# mcu_board_b.net
KiCad netlist of a schematic drawn in EAGLE
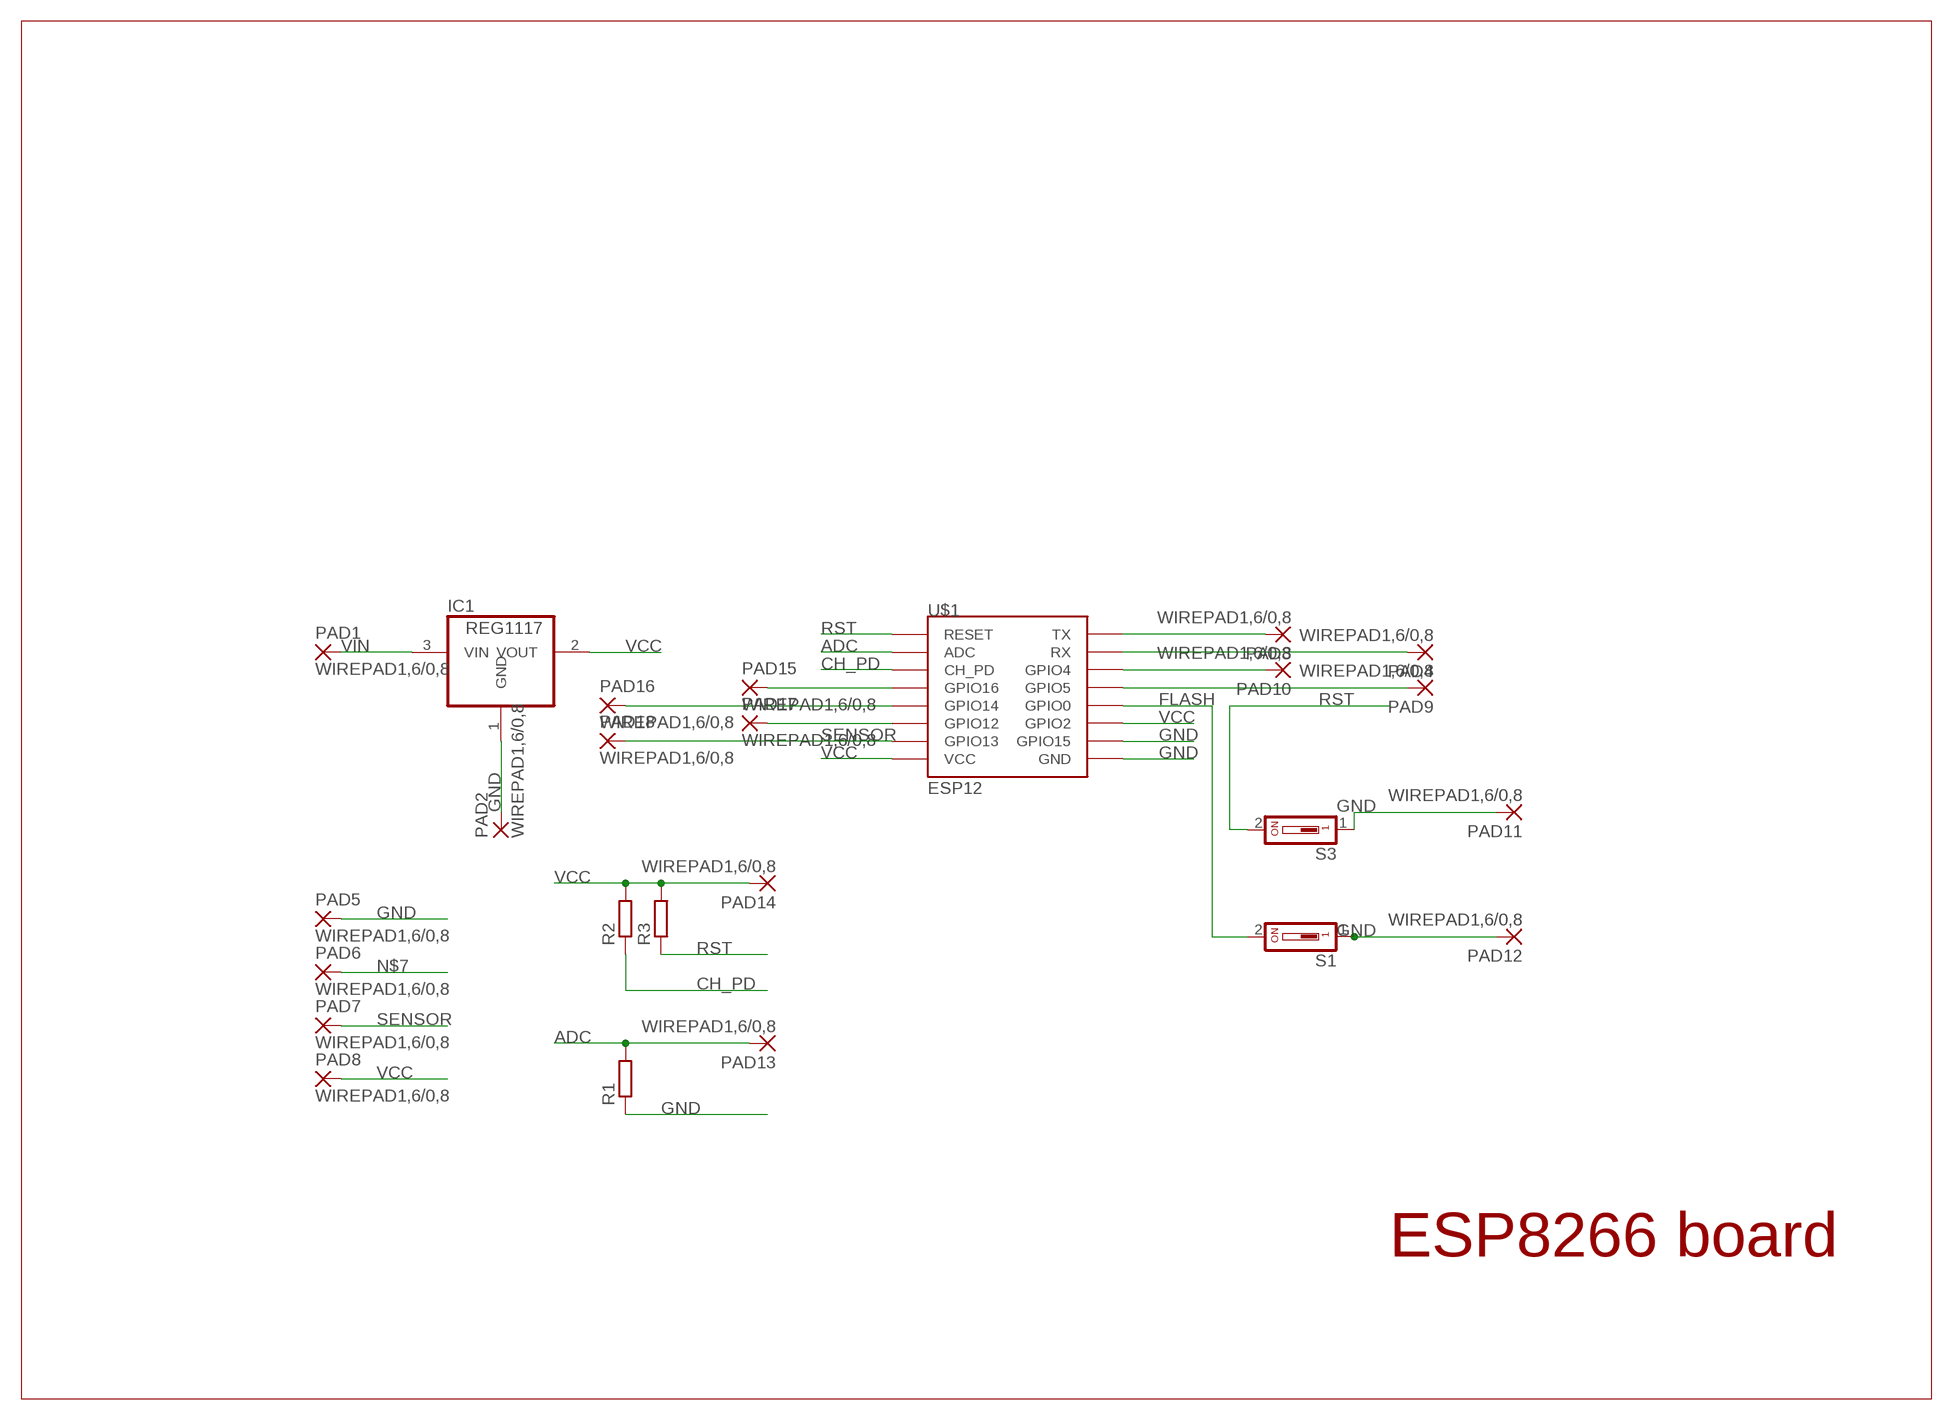
[diagram p0: schematic, sheet 1]

(export (version "E")
  (design (tool "Eeschema 10.0.6"))
  (components
    (comp (ref "IC1")
      (value "REG1117")
      (footprint "eagle-import:SOT223")
      (libsource (lib "eagle-import") (part "REG1117"))
    )
    (comp (ref "PAD1")
      (value "WIREPAD1,6/0,8")
      (footprint "eagle-import:1,6_0,8")
      (libsource (lib "eagle-import") (part "WIREPAD1,6/0,8"))
    )
    (comp (ref "PAD2")
      (value "WIREPAD1,6/0,8")
      (footprint "eagle-import:1,6_0,8")
      (libsource (lib "eagle-import") (part "WIREPAD1,6/0,8"))
    )
    (comp (ref "PAD3")
      (value "WIREPAD1,6/0,8")
      (footprint "eagle-import:1,6_0,8")
      (libsource (lib "eagle-import") (part "WIREPAD1,6/0,8"))
    )
    (comp (ref "PAD4")
      (value "WIREPAD1,6/0,8")
      (footprint "eagle-import:1,6_0,8")
      (libsource (lib "eagle-import") (part "WIREPAD1,6/0,8"))
    )
    (comp (ref "PAD5")
      (value "WIREPAD1,6/0,8")
      (footprint "eagle-import:1,6_0,8")
      (libsource (lib "eagle-import") (part "WIREPAD1,6/0,8"))
    )
    (comp (ref "PAD6")
      (value "WIREPAD1,6/0,8")
      (footprint "eagle-import:1,6_0,8")
      (libsource (lib "eagle-import") (part "WIREPAD1,6/0,8"))
    )
    (comp (ref "PAD7")
      (value "WIREPAD1,6/0,8")
      (footprint "eagle-import:1,6_0,8")
      (libsource (lib "eagle-import") (part "WIREPAD1,6/0,8"))
    )
    (comp (ref "PAD8")
      (value "WIREPAD1,6/0,8")
      (footprint "eagle-import:1,6_0,8")
      (libsource (lib "eagle-import") (part "WIREPAD1,6/0,8"))
    )
    (comp (ref "PAD9")
      (value "WIREPAD1,6/0,8")
      (footprint "eagle-import:1,6_0,8")
      (libsource (lib "eagle-import") (part "WIREPAD1,6/0,8"))
    )
    (comp (ref "PAD10")
      (value "WIREPAD1,6/0,8")
      (footprint "eagle-import:1,6_0,8")
      (libsource (lib "eagle-import") (part "WIREPAD1,6/0,8"))
    )
    (comp (ref "PAD11")
      (value "WIREPAD1,6/0,8")
      (footprint "eagle-import:1,6_0,8")
      (libsource (lib "eagle-import") (part "WIREPAD1,6/0,8"))
    )
    (comp (ref "PAD12")
      (value "WIREPAD1,6/0,8")
      (footprint "eagle-import:1,6_0,8")
      (libsource (lib "eagle-import") (part "WIREPAD1,6/0,8"))
    )
    (comp (ref "PAD13")
      (value "WIREPAD1,6/0,8")
      (footprint "eagle-import:1,6_0,8")
      (libsource (lib "eagle-import") (part "WIREPAD1,6/0,8"))
    )
    (comp (ref "PAD14")
      (value "WIREPAD1,6/0,8")
      (footprint "eagle-import:1,6_0,8")
      (libsource (lib "eagle-import") (part "WIREPAD1,6/0,8"))
    )
    (comp (ref "PAD15")
      (value "WIREPAD1,6/0,8")
      (footprint "eagle-import:1,6_0,8")
      (libsource (lib "eagle-import") (part "WIREPAD1,6/0,8"))
    )
    (comp (ref "PAD16")
      (value "WIREPAD1,6/0,8")
      (footprint "eagle-import:1,6_0,8")
      (libsource (lib "eagle-import") (part "WIREPAD1,6/0,8"))
    )
    (comp (ref "PAD17")
      (value "WIREPAD1,6/0,8")
      (footprint "eagle-import:1,6_0,8")
      (libsource (lib "eagle-import") (part "WIREPAD1,6/0,8"))
    )
    (comp (ref "PAD18")
      (value "WIREPAD1,6/0,8")
      (footprint "eagle-import:1,6_0,8")
      (libsource (lib "eagle-import") (part "WIREPAD1,6/0,8"))
    )
    (comp (ref "R1")
      (value "R-EU_M0805")
      (footprint "eagle-import:M0805")
      (libsource (lib "eagle-import") (part "R-EU_M0805"))
    )
    (comp (ref "R2")
      (value "R-EU_M0805")
      (footprint "eagle-import:M0805")
      (libsource (lib "eagle-import") (part "R-EU_M0805"))
    )
    (comp (ref "R3")
      (value "R-EU_M0805")
      (footprint "eagle-import:M0805")
      (libsource (lib "eagle-import") (part "R-EU_M0805"))
    )
    (comp (ref "S1")
      (value "DS01")
      (footprint "eagle-import:DS-01")
      (libsource (lib "eagle-import") (part "DS01"))
    )
    (comp (ref "S3")
      (value "DS01")
      (footprint "eagle-import:DS-01")
      (libsource (lib "eagle-import") (part "DS01"))
    )
    (comp (ref "U$1")
      (value "ESP12")
      (footprint "eagle-import:ESP12")
      (libsource (lib "eagle-import") (part "ESP12"))
    )
  )
  (nets
    (net (code "1") (name "/ADC") (class "Default")
      (node (ref "PAD13") (pin "1") (pinfunction "P_1") (pintype "passive"))
      (node (ref "R1") (pin "2") (pinfunction "2_2") (pintype "passive"))
      (node (ref "U$1") (pin "ADC") (pinfunction "ADC_ADC") (pintype "bidirectional"))
    )
    (net (code "2") (name "/CH_PD") (class "Default")
      (node (ref "R2") (pin "1") (pinfunction "1_1") (pintype "passive"))
      (node (ref "U$1") (pin "CH_PD") (pinfunction "CH_PD_CH_PD") (pintype "bidirectional"))
    )
    (net (code "3") (name "/FLASH") (class "Default")
      (node (ref "S1") (pin "2") (pinfunction "2_2") (pintype "passive"))
      (node (ref "U$1") (pin "GPIO0") (pinfunction "GPIO0_GPIO0") (pintype "bidirectional"))
    )
    (net (code "4") (name "/GND") (class "Default")
      (node (ref "IC1") (pin "1") (pinfunction "GND_1") (pintype "power_in"))
      (node (ref "PAD11") (pin "1") (pinfunction "P_1") (pintype "passive"))
      (node (ref "PAD12") (pin "1") (pinfunction "P_1") (pintype "passive"))
      (node (ref "PAD2") (pin "1") (pinfunction "P_1") (pintype "passive"))
      (node (ref "PAD5") (pin "1") (pinfunction "P_1") (pintype "passive"))
      (node (ref "R1") (pin "1") (pinfunction "1_1") (pintype "passive"))
      (node (ref "S1") (pin "1") (pinfunction "1_1") (pintype "passive"))
      (node (ref "S3") (pin "1") (pinfunction "1_1") (pintype "passive"))
      (node (ref "U$1") (pin "GND") (pinfunction "GND_GND") (pintype "bidirectional"))
      (node (ref "U$1") (pin "GPIO15") (pinfunction "GPIO15_GPIO15") (pintype "bidirectional"))
    )
    (net (code "5") (name "/N$7") (class "Default")
      (node (ref "PAD6") (pin "1") (pinfunction "P_1") (pintype "passive"))
    )
    (net (code "6") (name "/RST") (class "Default")
      (node (ref "R3") (pin "1") (pinfunction "1_1") (pintype "passive"))
      (node (ref "S3") (pin "2") (pinfunction "2_2") (pintype "passive"))
      (node (ref "U$1") (pin "RESET") (pinfunction "RESET_RESET") (pintype "bidirectional"))
    )
    (net (code "7") (name "/SENSOR") (class "Default")
      (node (ref "PAD18") (pin "1") (pinfunction "P_1") (pintype "passive"))
      (node (ref "PAD7") (pin "1") (pinfunction "P_1") (pintype "passive"))
      (node (ref "U$1") (pin "GPIO13") (pinfunction "GPIO13_GPIO13") (pintype "bidirectional"))
    )
    (net (code "8") (name "/VCC") (class "Default")
      (node (ref "IC1") (pin "2") (pinfunction "VOUT_2") (pintype "output"))
      (node (ref "PAD14") (pin "1") (pinfunction "P_1") (pintype "passive"))
      (node (ref "PAD8") (pin "1") (pinfunction "P_1") (pintype "passive"))
      (node (ref "R2") (pin "2") (pinfunction "2_2") (pintype "passive"))
      (node (ref "R3") (pin "2") (pinfunction "2_2") (pintype "passive"))
      (node (ref "U$1") (pin "GPIO2") (pinfunction "GPIO2_GPIO2") (pintype "bidirectional"))
      (node (ref "U$1") (pin "VCC") (pinfunction "VCC_VCC") (pintype "bidirectional"))
    )
    (net (code "9") (name "/VIN") (class "Default")
      (node (ref "IC1") (pin "3") (pinfunction "VIN_3") (pintype "input"))
      (node (ref "PAD1") (pin "1") (pinfunction "P_1") (pintype "passive"))
    )
    (net (code "10") (name "Net-(PAD3-P)") (class "Default")
      (node (ref "PAD3") (pin "1") (pinfunction "P_1") (pintype "passive"))
      (node (ref "U$1") (pin "TX") (pinfunction "TX_TX") (pintype "bidirectional"))
    )
    (net (code "11") (name "Net-(PAD4-P)") (class "Default")
      (node (ref "PAD4") (pin "1") (pinfunction "P_1") (pintype "passive"))
      (node (ref "U$1") (pin "RX") (pinfunction "RX_RX") (pintype "bidirectional"))
    )
    (net (code "12") (name "Net-(PAD9-P)") (class "Default")
      (node (ref "PAD9") (pin "1") (pinfunction "P_1") (pintype "passive"))
      (node (ref "U$1") (pin "GPIO5") (pinfunction "GPIO5_GPIO5") (pintype "bidirectional"))
    )
    (net (code "13") (name "Net-(PAD10-P)") (class "Default")
      (node (ref "PAD10") (pin "1") (pinfunction "P_1") (pintype "passive"))
      (node (ref "U$1") (pin "GPIO4") (pinfunction "GPIO4_GPIO4") (pintype "bidirectional"))
    )
    (net (code "14") (name "Net-(PAD15-P)") (class "Default")
      (node (ref "PAD15") (pin "1") (pinfunction "P_1") (pintype "passive"))
      (node (ref "U$1") (pin "GPIO16") (pinfunction "GPIO16_GPIO16") (pintype "bidirectional"))
    )
    (net (code "15") (name "Net-(PAD16-P)") (class "Default")
      (node (ref "PAD16") (pin "1") (pinfunction "P_1") (pintype "passive"))
      (node (ref "U$1") (pin "GPIO14") (pinfunction "GPIO14_GPIO14") (pintype "bidirectional"))
    )
    (net (code "16") (name "Net-(PAD17-P)") (class "Default")
      (node (ref "PAD17") (pin "1") (pinfunction "P_1") (pintype "passive"))
      (node (ref "U$1") (pin "GPIO12") (pinfunction "GPIO12_GPIO12") (pintype "bidirectional"))
    )
  )
)
